# PinOut_5.net
KiCad netlist of a schematic drawn in EAGLE
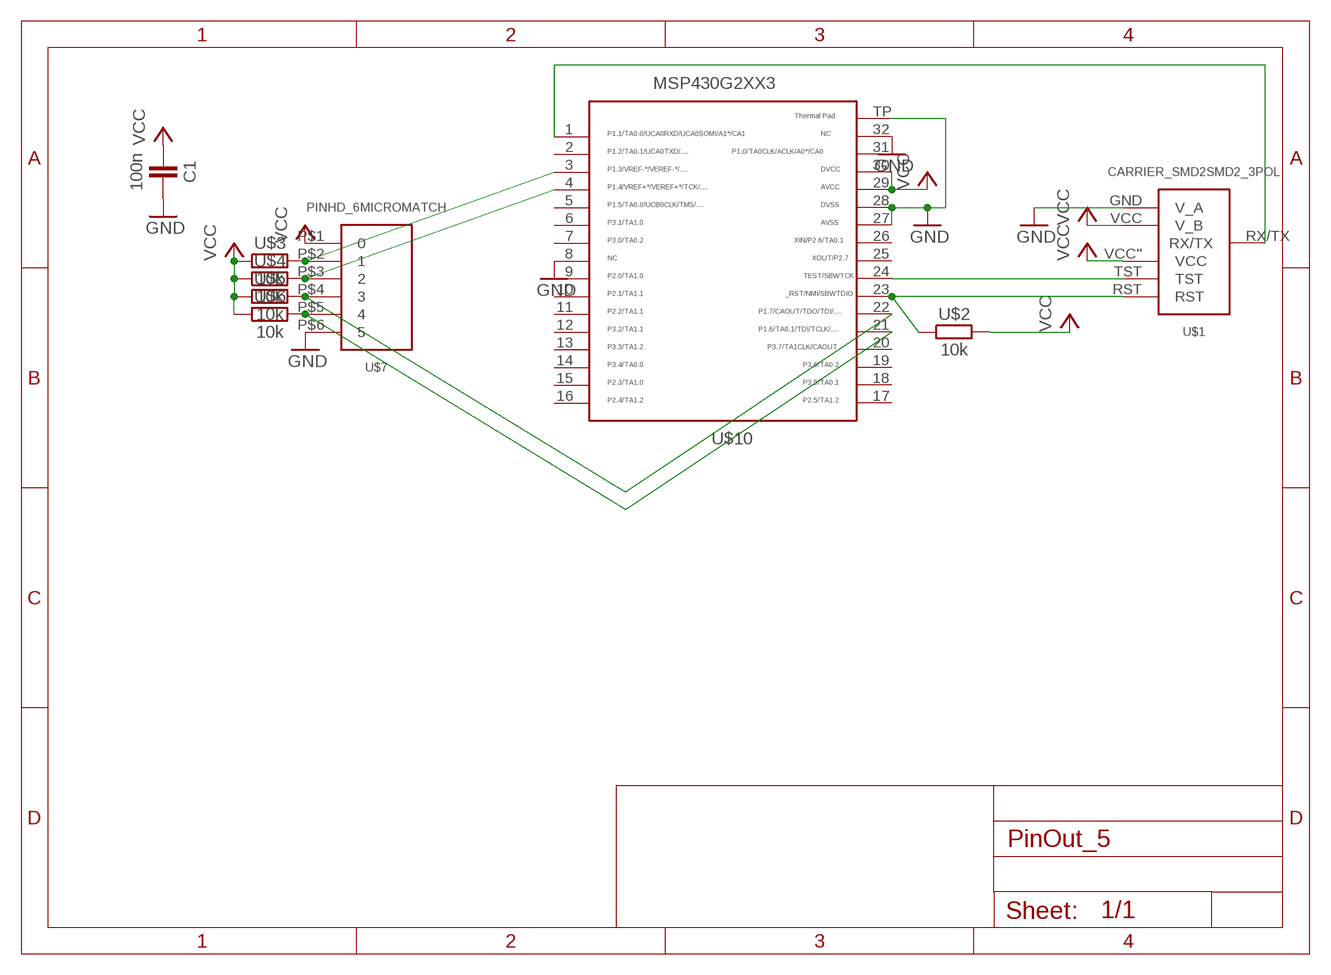
[diagram p0: schematic, sheet 1]

(export (version "E")
  (design (tool "Eeschema 10.0.6"))
  (components
    (comp (ref "C1")
      (value "100n")
      (footprint "eagle-import:603")
      (libsource (lib "eagle-import") (part "CAPACITOR"))
    )
    (comp (ref "U$1")
      (value "CARRIER_SMD2SMD2_3POL")
      (footprint "eagle-import:CARRIER_SMD2_3POL")
      (libsource (lib "eagle-import") (part "CARRIER_SMD2SMD2_3POL"))
    )
    (comp (ref "U$2")
      (value "10k")
      (footprint "eagle-import:603")
      (libsource (lib "eagle-import") (part "RESISTOR0603"))
    )
    (comp (ref "U$3")
      (value "10k")
      (footprint "eagle-import:603")
      (libsource (lib "eagle-import") (part "RESISTOR0603"))
    )
    (comp (ref "U$4")
      (value "10k")
      (footprint "eagle-import:603")
      (libsource (lib "eagle-import") (part "RESISTOR0603"))
    )
    (comp (ref "U$5")
      (value "10k")
      (footprint "eagle-import:603")
      (libsource (lib "eagle-import") (part "RESISTOR0603"))
    )
    (comp (ref "U$6")
      (value "10k")
      (footprint "eagle-import:603")
      (libsource (lib "eagle-import") (part "RESISTOR0603"))
    )
    (comp (ref "U$7")
      (value "PINHD_6MICROMATCH")
      (footprint "eagle-import:MICROMATCH6POL")
      (libsource (lib "eagle-import") (part "PINHD_6MICROMATCH"))
    )
    (comp (ref "U$10")
      (value "MSP430G2553")
      (footprint "eagle-import:QFN32")
      (libsource (lib "eagle-import") (part "MSP430G2553"))
    )
  )
  (nets
    (net (code "1") (name "GND") (class "Default")
      (node (ref "C1") (pin "2") (pinfunction "2_2") (pintype "passive"))
      (node (ref "U$1") (pin "GND") (pinfunction "V_A_GND") (pintype "bidirectional"))
      (node (ref "U$10") (pin "27") (pinfunction "27_27") (pintype "bidirectional"))
      (node (ref "U$10") (pin "28") (pinfunction "28_28") (pintype "bidirectional"))
      (node (ref "U$10") (pin "32") (pinfunction "32_32") (pintype "bidirectional"))
      (node (ref "U$10") (pin "8") (pinfunction "8_8") (pintype "bidirectional"))
      (node (ref "U$10") (pin "TP") (pinfunction "TP_TP") (pintype "bidirectional"))
      (node (ref "U$7") (pin "P$6") (pinfunction "5_P$6") (pintype "bidirectional"))
    )
    (net (code "2") (name "Net-(U$1-PadRST)") (class "Default")
      (node (ref "U$1") (pin "RST") (pinfunction "RST_RST") (pintype "bidirectional"))
      (node (ref "U$10") (pin "23") (pinfunction "23_23") (pintype "bidirectional"))
      (node (ref "U$2") (pin "1") (pinfunction "1_1") (pintype "passive"))
    )
    (net (code "3") (name "Net-(U$1-PadRX{slash}TX)") (class "Default")
      (node (ref "U$1") (pin "RX/TX") (pinfunction "RX/TX_RX/TX") (pintype "bidirectional"))
      (node (ref "U$10") (pin "1") (pinfunction "1_1") (pintype "bidirectional"))
    )
    (net (code "4") (name "Net-(U$1-PadTST)") (class "Default")
      (node (ref "U$1") (pin "TST") (pinfunction "TST_TST") (pintype "bidirectional"))
      (node (ref "U$10") (pin "24") (pinfunction "24_24") (pintype "bidirectional"))
    )
    (net (code "5") (name "Net-(U$7-1)") (class "Default")
      (node (ref "U$10") (pin "3") (pinfunction "3_3") (pintype "bidirectional"))
      (node (ref "U$3") (pin "2") (pinfunction "2_2") (pintype "passive"))
      (node (ref "U$7") (pin "P$2") (pinfunction "1_P$2") (pintype "bidirectional"))
    )
    (net (code "6") (name "Net-(U$7-2)") (class "Default")
      (node (ref "U$10") (pin "4") (pinfunction "4_4") (pintype "bidirectional"))
      (node (ref "U$4") (pin "2") (pinfunction "2_2") (pintype "passive"))
      (node (ref "U$7") (pin "P$3") (pinfunction "2_P$3") (pintype "bidirectional"))
    )
    (net (code "7") (name "Net-(U$7-3)") (class "Default")
      (node (ref "U$10") (pin "22") (pinfunction "22_22") (pintype "bidirectional"))
      (node (ref "U$5") (pin "2") (pinfunction "2_2") (pintype "passive"))
      (node (ref "U$7") (pin "P$4") (pinfunction "3_P$4") (pintype "bidirectional"))
    )
    (net (code "8") (name "Net-(U$7-4)") (class "Default")
      (node (ref "U$10") (pin "21") (pinfunction "21_21") (pintype "bidirectional"))
      (node (ref "U$6") (pin "2") (pinfunction "2_2") (pintype "passive"))
      (node (ref "U$7") (pin "P$5") (pinfunction "4_P$5") (pintype "bidirectional"))
    )
    (net (code "9") (name "VCC") (class "Default")
      (node (ref "C1") (pin "1") (pinfunction "1_1") (pintype "passive"))
      (node (ref "U$1") (pin "VCC") (pinfunction "V_B_VCC") (pintype "bidirectional"))
      (node (ref "U$1") (pin "VCC''") (pinfunction "VCC_VCC''") (pintype "bidirectional"))
      (node (ref "U$10") (pin "29") (pinfunction "29_29") (pintype "bidirectional"))
      (node (ref "U$10") (pin "30") (pinfunction "30_30") (pintype "bidirectional"))
      (node (ref "U$2") (pin "2") (pinfunction "2_2") (pintype "passive"))
      (node (ref "U$3") (pin "1") (pinfunction "1_1") (pintype "passive"))
      (node (ref "U$4") (pin "1") (pinfunction "1_1") (pintype "passive"))
      (node (ref "U$5") (pin "1") (pinfunction "1_1") (pintype "passive"))
      (node (ref "U$6") (pin "1") (pinfunction "1_1") (pintype "passive"))
      (node (ref "U$7") (pin "P$1") (pinfunction "0_P$1") (pintype "bidirectional"))
    )
    (net (code "10") (name "unconnected-(U$10-Pad2)") (class "Default")
      (node (ref "U$10") (pin "2") (pinfunction "2_2") (pintype "bidirectional"))
    )
    (net (code "11") (name "unconnected-(U$10-Pad5)") (class "Default")
      (node (ref "U$10") (pin "5") (pinfunction "5_5") (pintype "bidirectional"))
    )
    (net (code "12") (name "unconnected-(U$10-Pad6)") (class "Default")
      (node (ref "U$10") (pin "6") (pinfunction "6_6") (pintype "bidirectional"))
    )
    (net (code "13") (name "unconnected-(U$10-Pad7)") (class "Default")
      (node (ref "U$10") (pin "7") (pinfunction "7_7") (pintype "bidirectional"))
    )
    (net (code "14") (name "unconnected-(U$10-Pad9)") (class "Default")
      (node (ref "U$10") (pin "9") (pinfunction "9_9") (pintype "bidirectional"))
    )
    (net (code "15") (name "unconnected-(U$10-Pad10)") (class "Default")
      (node (ref "U$10") (pin "10") (pinfunction "10_10") (pintype "bidirectional"))
    )
    (net (code "16") (name "unconnected-(U$10-Pad11)") (class "Default")
      (node (ref "U$10") (pin "11") (pinfunction "11_11") (pintype "bidirectional"))
    )
    (net (code "17") (name "unconnected-(U$10-Pad12)") (class "Default")
      (node (ref "U$10") (pin "12") (pinfunction "12_12") (pintype "bidirectional"))
    )
    (net (code "18") (name "unconnected-(U$10-Pad13)") (class "Default")
      (node (ref "U$10") (pin "13") (pinfunction "13_13") (pintype "bidirectional"))
    )
    (net (code "19") (name "unconnected-(U$10-Pad14)") (class "Default")
      (node (ref "U$10") (pin "14") (pinfunction "14_14") (pintype "bidirectional"))
    )
    (net (code "20") (name "unconnected-(U$10-Pad15)") (class "Default")
      (node (ref "U$10") (pin "15") (pinfunction "15_15") (pintype "bidirectional"))
    )
    (net (code "21") (name "unconnected-(U$10-Pad16)") (class "Default")
      (node (ref "U$10") (pin "16") (pinfunction "16_16") (pintype "bidirectional"))
    )
    (net (code "22") (name "unconnected-(U$10-Pad17)") (class "Default")
      (node (ref "U$10") (pin "17") (pinfunction "17_17") (pintype "bidirectional"))
    )
    (net (code "23") (name "unconnected-(U$10-Pad18)") (class "Default")
      (node (ref "U$10") (pin "18") (pinfunction "18_18") (pintype "bidirectional"))
    )
    (net (code "24") (name "unconnected-(U$10-Pad19)") (class "Default")
      (node (ref "U$10") (pin "19") (pinfunction "19_19") (pintype "bidirectional"))
    )
    (net (code "25") (name "unconnected-(U$10-Pad20)") (class "Default")
      (node (ref "U$10") (pin "20") (pinfunction "20_20") (pintype "bidirectional"))
    )
    (net (code "26") (name "unconnected-(U$10-Pad25)") (class "Default")
      (node (ref "U$10") (pin "25") (pinfunction "25_25") (pintype "bidirectional"))
    )
    (net (code "27") (name "unconnected-(U$10-Pad26)") (class "Default")
      (node (ref "U$10") (pin "26") (pinfunction "26_26") (pintype "bidirectional"))
    )
    (net (code "28") (name "unconnected-(U$10-Pad31)") (class "Default")
      (node (ref "U$10") (pin "31") (pinfunction "31_31") (pintype "bidirectional"))
    )
  )
)
